# stm32hw01.net
KiCad netlist of a schematic drawn in EAGLE
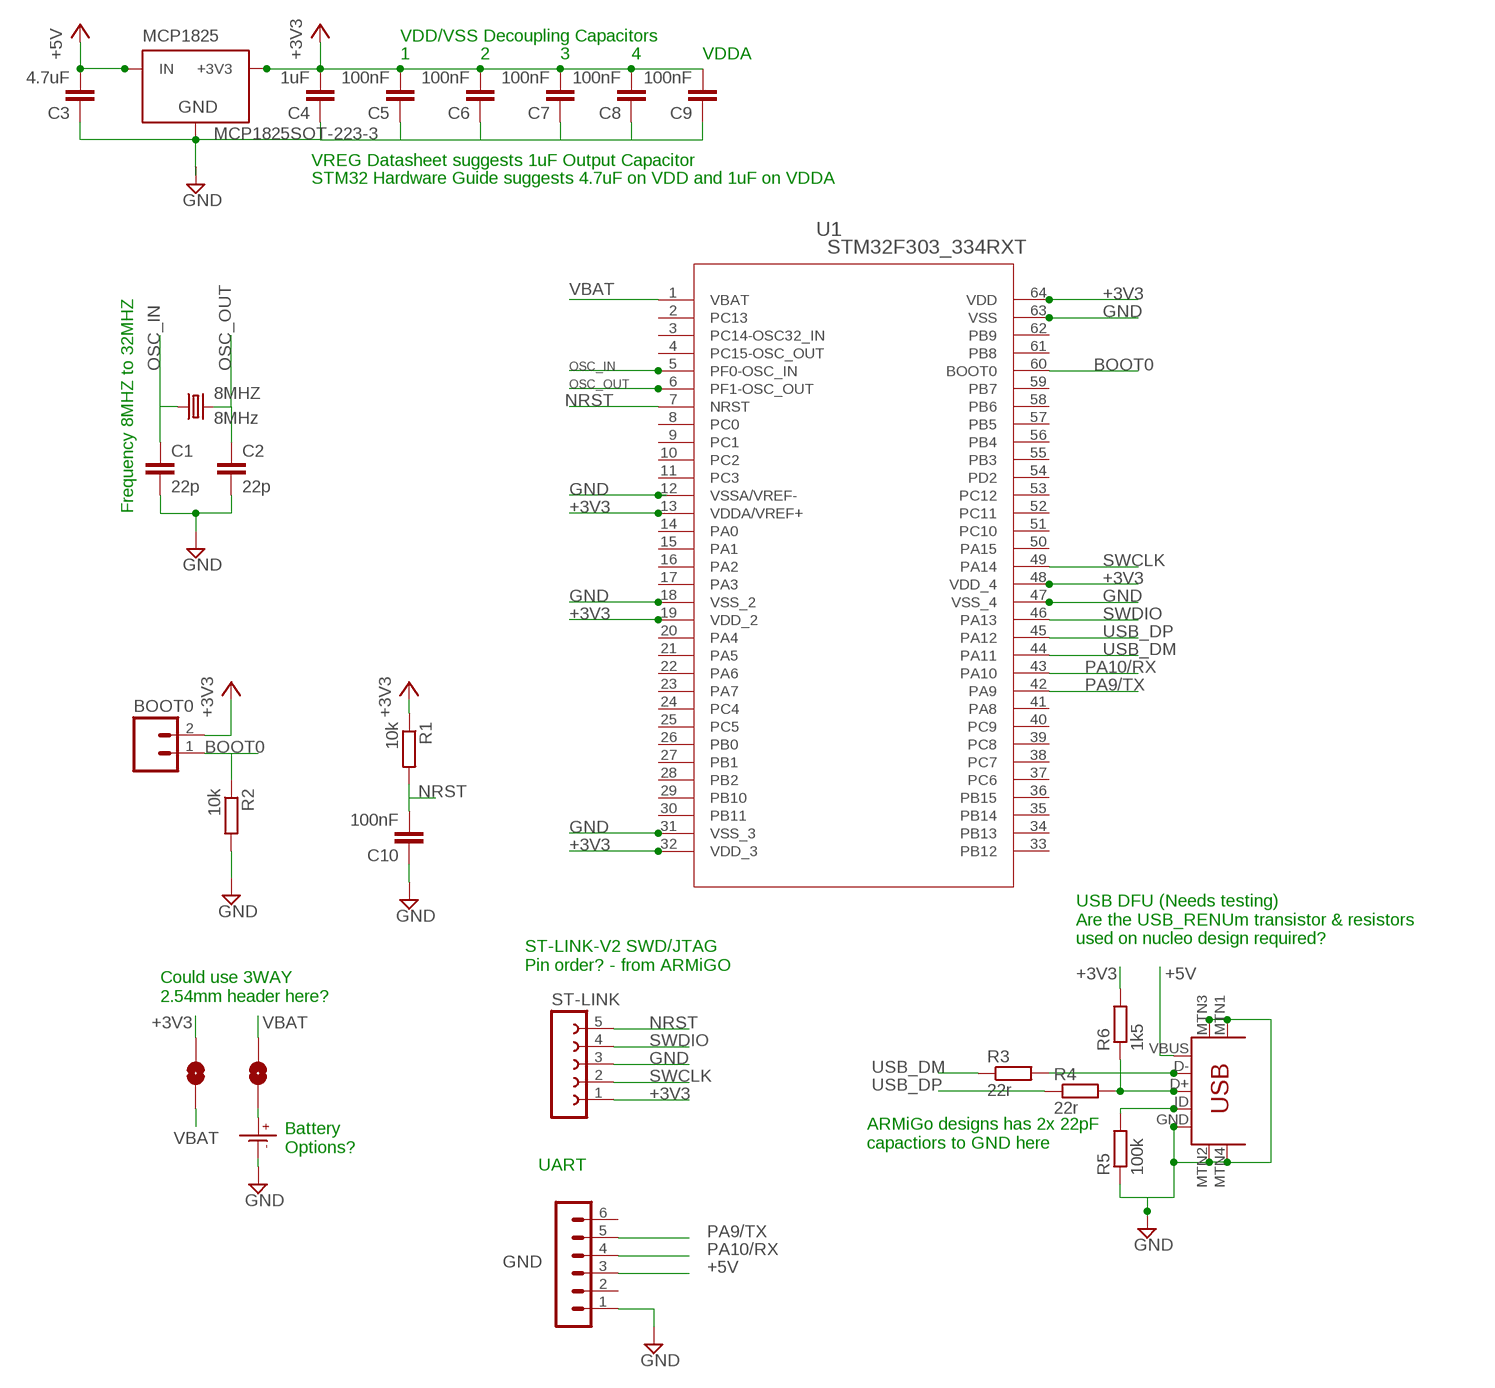
[diagram p0: schematic, sheet 1]

(export (version "E")
  (design (tool "Eeschema 10.0.6"))
  (components
    (comp (ref "3V3")
      (value "SOLDERJUMPERNO")
      (footprint "eagle-import:SJ_2S-NO")
      (libsource (lib "eagle-import") (part "SOLDERJUMPERNO"))
    )
    (comp (ref "8MHZ")
      (value "8MHz")
      (footprint "eagle-import:CRYSTAL-SMD-5X3")
      (libsource (lib "eagle-import") (part "CRYSTAL5X3"))
    )
    (comp (ref "BATTERY")
      (value "SOLDERJUMPERNO")
      (footprint "eagle-import:SJ_2S-NO")
      (libsource (lib "eagle-import") (part "SOLDERJUMPERNO"))
    )
    (comp (ref "BOOT0")
      (value "M02PTH")
      (footprint "eagle-import:1X02")
      (libsource (lib "eagle-import") (part "M02PTH"))
    )
    (comp (ref "C1")
      (value "22p")
      (footprint "eagle-import:C0603")
      (libsource (lib "eagle-import") (part "C-EUC0603"))
    )
    (comp (ref "C2")
      (value "22p")
      (footprint "eagle-import:C0603")
      (libsource (lib "eagle-import") (part "C-EUC0603"))
    )
    (comp (ref "C3")
      (value "4.7uF")
      (footprint "eagle-import:C0603")
      (libsource (lib "eagle-import") (part "C-EUC0603"))
    )
    (comp (ref "C4")
      (value "1uF")
      (footprint "eagle-import:C0603")
      (libsource (lib "eagle-import") (part "C-EUC0603"))
    )
    (comp (ref "C5")
      (value "100nF")
      (footprint "eagle-import:C0603")
      (libsource (lib "eagle-import") (part "C-EUC0603"))
    )
    (comp (ref "C6")
      (value "100nF")
      (footprint "eagle-import:C0603")
      (libsource (lib "eagle-import") (part "C-EUC0603"))
    )
    (comp (ref "C7")
      (value "100nF")
      (footprint "eagle-import:C0603")
      (libsource (lib "eagle-import") (part "C-EUC0603"))
    )
    (comp (ref "C8")
      (value "100nF")
      (footprint "eagle-import:C0603")
      (libsource (lib "eagle-import") (part "C-EUC0603"))
    )
    (comp (ref "C9")
      (value "100nF")
      (footprint "eagle-import:C0603")
      (libsource (lib "eagle-import") (part "C-EUC0603"))
    )
    (comp (ref "C10")
      (value "100nF")
      (footprint "eagle-import:C0603")
      (libsource (lib "eagle-import") (part "C-EUC0603"))
    )
    (comp (ref "CR1220")
      (value "CR1220SMD")
      (footprint "eagle-import:CR1220SMD")
      (fields (field (name "MPN") "Harwin S8411-45R"))
      (libsource (lib "eagle-import") (part "CR1220SMD"))
    )
    (comp (ref "GND")
      (value "UART")
      (footprint "eagle-import:MA06-1")
      (libsource (lib "eagle-import") (part "MA06-1"))
    )
    (comp (ref "MCP1825")
      (value "MCP1825SOT-223-3")
      (footprint "eagle-import:SOT-223")
      (libsource (lib "eagle-import") (part "MCP1825SOT-223-3"))
    )
    (comp (ref "R1")
      (value "10k")
      (footprint "eagle-import:R0603")
      (libsource (lib "eagle-import") (part "R-EU_R0603"))
    )
    (comp (ref "R2")
      (value "10k")
      (footprint "eagle-import:R0603")
      (libsource (lib "eagle-import") (part "R-EU_R0603"))
    )
    (comp (ref "R3")
      (value "22r")
      (footprint "eagle-import:R0603")
      (libsource (lib "eagle-import") (part "R-EU_R0603"))
    )
    (comp (ref "R4")
      (value "22r")
      (footprint "eagle-import:R0603")
      (libsource (lib "eagle-import") (part "R-EU_R0603"))
    )
    (comp (ref "R5")
      (value "100k")
      (footprint "eagle-import:R0603")
      (libsource (lib "eagle-import") (part "R-EU_R0603"))
    )
    (comp (ref "R6")
      (value "1k5")
      (footprint "eagle-import:R0603")
      (libsource (lib "eagle-import") (part "R-EU_R0603"))
    )
    (comp (ref "ST-LINK")
      (value "FE05-1")
      (footprint "eagle-import:FE05-1")
      (libsource (lib "eagle-import") (part "FE05-1"))
    )
    (comp (ref "U$10")
      (value "USB-MINIB-5PIN")
      (footprint "eagle-import:USB-MINIB-CISECO")
      (libsource (lib "eagle-import") (part "USB-MINIB-5PIN"))
    )
    (comp (ref "U1")
      (value "STM32F303_334RXT")
      (footprint "eagle-import:LQFP64-10X10MM")
      (fields (field (name "MANUFACTURER_PART_NUMBER") "stm32f303_334rxt"))
      (libsource (lib "eagle-import") (part "STM32F303_334RXT"))
    )
  )
  (nets
    (net (code "1") (name "+3V3") (class "Default")
      (node (ref "3V3") (pin "1") (pinfunction "1_1") (pintype "passive"))
      (node (ref "BOOT0") (pin "2") (pinfunction "2_2") (pintype "passive"))
      (node (ref "C4") (pin "2") (pinfunction "2_2") (pintype "passive"))
      (node (ref "C5") (pin "2") (pinfunction "2_2") (pintype "passive"))
      (node (ref "C6") (pin "2") (pinfunction "2_2") (pintype "passive"))
      (node (ref "C7") (pin "2") (pinfunction "2_2") (pintype "passive"))
      (node (ref "C8") (pin "2") (pinfunction "2_2") (pintype "passive"))
      (node (ref "C9") (pin "2") (pinfunction "2_2") (pintype "passive"))
      (node (ref "MCP1825") (pin "3") (pinfunction "+3V3_3") (pintype "power_in"))
      (node (ref "R1") (pin "1") (pinfunction "1_1") (pintype "passive"))
      (node (ref "R6") (pin "2") (pinfunction "2_2") (pintype "passive"))
      (node (ref "ST-LINK") (pin "1") (pinfunction "1_1") (pintype "passive"))
      (node (ref "U1") (pin "13") (pinfunction "VDDA/VREF+_13") (pintype "power_in"))
      (node (ref "U1") (pin "19") (pinfunction "VDD_2_19") (pintype "power_in"))
      (node (ref "U1") (pin "32") (pinfunction "VDD_3_32") (pintype "power_in"))
      (node (ref "U1") (pin "48") (pinfunction "VDD_4_48") (pintype "power_in"))
      (node (ref "U1") (pin "64") (pinfunction "VDD_64") (pintype "power_in"))
    )
    (net (code "2") (name "+5V") (class "Default")
      (node (ref "C3") (pin "2") (pinfunction "2_2") (pintype "passive"))
      (node (ref "GND") (pin "3") (pinfunction "3_3") (pintype "passive"))
      (node (ref "MCP1825") (pin "1") (pinfunction "IN_1") (pintype "power_in"))
      (node (ref "U$10") (pin "VBUS") (pinfunction "VBUS_VBUS") (pintype "bidirectional"))
    )
    (net (code "3") (name "/BOOT0") (class "Default")
      (node (ref "BOOT0") (pin "1") (pinfunction "1_1") (pintype "passive"))
      (node (ref "R2") (pin "1") (pinfunction "1_1") (pintype "passive"))
      (node (ref "U1") (pin "60") (pinfunction "BOOT0_60") (pintype "input"))
    )
    (net (code "4") (name "/NRST") (class "Default")
      (node (ref "C10") (pin "2") (pinfunction "2_2") (pintype "passive"))
      (node (ref "R1") (pin "2") (pinfunction "2_2") (pintype "passive"))
      (node (ref "ST-LINK") (pin "5") (pinfunction "5_5") (pintype "passive"))
      (node (ref "U1") (pin "7") (pinfunction "NRST_7") (pintype "bidirectional"))
    )
    (net (code "5") (name "/OSC_IN") (class "Default")
      (node (ref "8MHZ") (pin "1") (pinfunction "1_1") (pintype "passive"))
      (node (ref "C1") (pin "1") (pinfunction "1_1") (pintype "passive"))
      (node (ref "U1") (pin "5") (pinfunction "PF0-OSC_IN_5") (pintype "bidirectional"))
    )
    (net (code "6") (name "/OSC_OUT") (class "Default")
      (node (ref "8MHZ") (pin "3") (pinfunction "2_3") (pintype "passive"))
      (node (ref "C2") (pin "1") (pinfunction "1_1") (pintype "passive"))
      (node (ref "U1") (pin "6") (pinfunction "PF1-OSC_OUT_6") (pintype "bidirectional"))
    )
    (net (code "7") (name "/PA9{slash}TX") (class "Default")
      (node (ref "GND") (pin "5") (pinfunction "5_5") (pintype "passive"))
      (node (ref "U1") (pin "42") (pinfunction "PA9_42") (pintype "bidirectional"))
    )
    (net (code "8") (name "/PA10{slash}RX") (class "Default")
      (node (ref "GND") (pin "4") (pinfunction "4_4") (pintype "passive"))
      (node (ref "U1") (pin "43") (pinfunction "PA10_43") (pintype "bidirectional"))
    )
    (net (code "9") (name "/SWCLK") (class "Default")
      (node (ref "ST-LINK") (pin "2") (pinfunction "2_2") (pintype "passive"))
      (node (ref "U1") (pin "49") (pinfunction "PA14_49") (pintype "bidirectional"))
    )
    (net (code "10") (name "/SWDIO") (class "Default")
      (node (ref "ST-LINK") (pin "4") (pinfunction "4_4") (pintype "passive"))
      (node (ref "U1") (pin "46") (pinfunction "PA13_46") (pintype "bidirectional"))
    )
    (net (code "11") (name "/USB_DM") (class "Default")
      (node (ref "R3") (pin "1") (pinfunction "1_1") (pintype "passive"))
      (node (ref "U1") (pin "44") (pinfunction "PA11_44") (pintype "bidirectional"))
    )
    (net (code "12") (name "/USB_DP") (class "Default")
      (node (ref "R4") (pin "1") (pinfunction "1_1") (pintype "passive"))
      (node (ref "U1") (pin "45") (pinfunction "PA12_45") (pintype "bidirectional"))
    )
    (net (code "13") (name "/VBAT") (class "Default")
      (node (ref "3V3") (pin "2") (pinfunction "2_2") (pintype "passive"))
      (node (ref "BATTERY") (pin "1") (pinfunction "1_1") (pintype "passive"))
      (node (ref "U1") (pin "1") (pinfunction "VBAT_1") (pintype "power_in"))
    )
    (net (code "14") (name "GND") (class "Default")
      (node (ref "C1") (pin "2") (pinfunction "2_2") (pintype "passive"))
      (node (ref "C10") (pin "1") (pinfunction "1_1") (pintype "passive"))
      (node (ref "C2") (pin "2") (pinfunction "2_2") (pintype "passive"))
      (node (ref "C3") (pin "1") (pinfunction "1_1") (pintype "passive"))
      (node (ref "C4") (pin "1") (pinfunction "1_1") (pintype "passive"))
      (node (ref "C5") (pin "1") (pinfunction "1_1") (pintype "passive"))
      (node (ref "C6") (pin "1") (pinfunction "1_1") (pintype "passive"))
      (node (ref "C7") (pin "1") (pinfunction "1_1") (pintype "passive"))
      (node (ref "C8") (pin "1") (pinfunction "1_1") (pintype "passive"))
      (node (ref "C9") (pin "1") (pinfunction "1_1") (pintype "passive"))
      (node (ref "CR1220") (pin "P-") (pinfunction "P$-_P-") (pintype "bidirectional"))
      (node (ref "GND") (pin "1") (pinfunction "1_1") (pintype "passive"))
      (node (ref "MCP1825") (pin "2") (pinfunction "GND_2") (pintype "power_in"))
      (node (ref "R2") (pin "2") (pinfunction "2_2") (pintype "passive"))
      (node (ref "R5") (pin "1") (pinfunction "1_1") (pintype "passive"))
      (node (ref "ST-LINK") (pin "3") (pinfunction "3_3") (pintype "passive"))
      (node (ref "U$10") (pin "GND") (pinfunction "GND_GND") (pintype "bidirectional"))
      (node (ref "U$10") (pin "MTN1") (pinfunction "MTN2_MTN1") (pintype "bidirectional"))
      (node (ref "U$10") (pin "MTN2") (pinfunction "MTN3_MTN2") (pintype "bidirectional"))
      (node (ref "U$10") (pin "MTN3") (pinfunction "MTN1_MTN3") (pintype "bidirectional"))
      (node (ref "U$10") (pin "MTN4") (pinfunction "MTN4_MTN4") (pintype "bidirectional"))
      (node (ref "U1") (pin "12") (pinfunction "VSSA/VREF-_12") (pintype "power_in"))
      (node (ref "U1") (pin "18") (pinfunction "VSS_2_18") (pintype "power_in"))
      (node (ref "U1") (pin "31") (pinfunction "VSS_3_31") (pintype "power_in"))
      (node (ref "U1") (pin "47") (pinfunction "VSS_4_47") (pintype "power_in"))
      (node (ref "U1") (pin "63") (pinfunction "VSS_63") (pintype "power_in"))
    )
    (net (code "15") (name "Net-(CR1220-P$+)") (class "Default")
      (node (ref "BATTERY") (pin "2") (pinfunction "2_2") (pintype "passive"))
      (node (ref "CR1220") (pin "P+") (pinfunction "P$+_P+") (pintype "bidirectional"))
    )
    (net (code "16") (name "Net-(R3-Pad2)") (class "Default")
      (node (ref "R3") (pin "2") (pinfunction "2_2") (pintype "passive"))
      (node (ref "U$10") (pin "D-") (pinfunction "D-_D-") (pintype "bidirectional"))
    )
    (net (code "17") (name "Net-(R4-Pad2)") (class "Default")
      (node (ref "R4") (pin "2") (pinfunction "2_2") (pintype "passive"))
      (node (ref "R6") (pin "1") (pinfunction "1_1") (pintype "passive"))
      (node (ref "U$10") (pin "D+") (pinfunction "D+_D+") (pintype "bidirectional"))
    )
    (net (code "18") (name "Net-(R5-Pad2)") (class "Default")
      (node (ref "R5") (pin "2") (pinfunction "2_2") (pintype "passive"))
      (node (ref "U$10") (pin "ID") (pinfunction "ID_ID") (pintype "bidirectional"))
    )
    (net (code "19") (name "unconnected-(GND-Pad2)") (class "Default")
      (node (ref "GND") (pin "2") (pinfunction "2_2") (pintype "passive"))
    )
    (net (code "20") (name "unconnected-(GND-Pad6)") (class "Default")
      (node (ref "GND") (pin "6") (pinfunction "6_6") (pintype "passive"))
    )
    (net (code "21") (name "unconnected-(U1-PA0-Pad14)") (class "Default")
      (node (ref "U1") (pin "14") (pinfunction "PA0_14") (pintype "bidirectional"))
    )
    (net (code "22") (name "unconnected-(U1-PA1-Pad15)") (class "Default")
      (node (ref "U1") (pin "15") (pinfunction "PA1_15") (pintype "bidirectional"))
    )
    (net (code "23") (name "unconnected-(U1-PA2-Pad16)") (class "Default")
      (node (ref "U1") (pin "16") (pinfunction "PA2_16") (pintype "bidirectional"))
    )
    (net (code "24") (name "unconnected-(U1-PA3-Pad17)") (class "Default")
      (node (ref "U1") (pin "17") (pinfunction "PA3_17") (pintype "bidirectional"))
    )
    (net (code "25") (name "unconnected-(U1-PA4-Pad20)") (class "Default")
      (node (ref "U1") (pin "20") (pinfunction "PA4_20") (pintype "bidirectional"))
    )
    (net (code "26") (name "unconnected-(U1-PA5-Pad21)") (class "Default")
      (node (ref "U1") (pin "21") (pinfunction "PA5_21") (pintype "bidirectional"))
    )
    (net (code "27") (name "unconnected-(U1-PA6-Pad22)") (class "Default")
      (node (ref "U1") (pin "22") (pinfunction "PA6_22") (pintype "bidirectional"))
    )
    (net (code "28") (name "unconnected-(U1-PA7-Pad23)") (class "Default")
      (node (ref "U1") (pin "23") (pinfunction "PA7_23") (pintype "bidirectional"))
    )
    (net (code "29") (name "unconnected-(U1-PA8-Pad41)") (class "Default")
      (node (ref "U1") (pin "41") (pinfunction "PA8_41") (pintype "bidirectional"))
    )
    (net (code "30") (name "unconnected-(U1-PA15-Pad50)") (class "Default")
      (node (ref "U1") (pin "50") (pinfunction "PA15_50") (pintype "bidirectional"))
    )
    (net (code "31") (name "unconnected-(U1-PB0-Pad26)") (class "Default")
      (node (ref "U1") (pin "26") (pinfunction "PB0_26") (pintype "bidirectional"))
    )
    (net (code "32") (name "unconnected-(U1-PB1-Pad27)") (class "Default")
      (node (ref "U1") (pin "27") (pinfunction "PB1_27") (pintype "bidirectional"))
    )
    (net (code "33") (name "unconnected-(U1-PB2-Pad28)") (class "Default")
      (node (ref "U1") (pin "28") (pinfunction "PB2_28") (pintype "bidirectional"))
    )
    (net (code "34") (name "unconnected-(U1-PB3-Pad55)") (class "Default")
      (node (ref "U1") (pin "55") (pinfunction "PB3_55") (pintype "bidirectional"))
    )
    (net (code "35") (name "unconnected-(U1-PB4-Pad56)") (class "Default")
      (node (ref "U1") (pin "56") (pinfunction "PB4_56") (pintype "bidirectional"))
    )
    (net (code "36") (name "unconnected-(U1-PB5-Pad57)") (class "Default")
      (node (ref "U1") (pin "57") (pinfunction "PB5_57") (pintype "bidirectional"))
    )
    (net (code "37") (name "unconnected-(U1-PB6-Pad58)") (class "Default")
      (node (ref "U1") (pin "58") (pinfunction "PB6_58") (pintype "bidirectional"))
    )
    (net (code "38") (name "unconnected-(U1-PB7-Pad59)") (class "Default")
      (node (ref "U1") (pin "59") (pinfunction "PB7_59") (pintype "bidirectional"))
    )
    (net (code "39") (name "unconnected-(U1-PB8-Pad61)") (class "Default")
      (node (ref "U1") (pin "61") (pinfunction "PB8_61") (pintype "bidirectional"))
    )
    (net (code "40") (name "unconnected-(U1-PB9-Pad62)") (class "Default")
      (node (ref "U1") (pin "62") (pinfunction "PB9_62") (pintype "bidirectional"))
    )
    (net (code "41") (name "unconnected-(U1-PB10-Pad29)") (class "Default")
      (node (ref "U1") (pin "29") (pinfunction "PB10_29") (pintype "bidirectional"))
    )
    (net (code "42") (name "unconnected-(U1-PB11-Pad30)") (class "Default")
      (node (ref "U1") (pin "30") (pinfunction "PB11_30") (pintype "bidirectional"))
    )
    (net (code "43") (name "unconnected-(U1-PB12-Pad33)") (class "Default")
      (node (ref "U1") (pin "33") (pinfunction "PB12_33") (pintype "bidirectional"))
    )
    (net (code "44") (name "unconnected-(U1-PB13-Pad34)") (class "Default")
      (node (ref "U1") (pin "34") (pinfunction "PB13_34") (pintype "bidirectional"))
    )
    (net (code "45") (name "unconnected-(U1-PB14-Pad35)") (class "Default")
      (node (ref "U1") (pin "35") (pinfunction "PB14_35") (pintype "bidirectional"))
    )
    (net (code "46") (name "unconnected-(U1-PB15-Pad36)") (class "Default")
      (node (ref "U1") (pin "36") (pinfunction "PB15_36") (pintype "bidirectional"))
    )
    (net (code "47") (name "unconnected-(U1-PC0-Pad8)") (class "Default")
      (node (ref "U1") (pin "8") (pinfunction "PC0_8") (pintype "bidirectional"))
    )
    (net (code "48") (name "unconnected-(U1-PC1-Pad9)") (class "Default")
      (node (ref "U1") (pin "9") (pinfunction "PC1_9") (pintype "bidirectional"))
    )
    (net (code "49") (name "unconnected-(U1-PC2-Pad10)") (class "Default")
      (node (ref "U1") (pin "10") (pinfunction "PC2_10") (pintype "bidirectional"))
    )
    (net (code "50") (name "unconnected-(U1-PC3-Pad11)") (class "Default")
      (node (ref "U1") (pin "11") (pinfunction "PC3_11") (pintype "bidirectional"))
    )
    (net (code "51") (name "unconnected-(U1-PC4-Pad24)") (class "Default")
      (node (ref "U1") (pin "24") (pinfunction "PC4_24") (pintype "bidirectional"))
    )
    (net (code "52") (name "unconnected-(U1-PC5-Pad25)") (class "Default")
      (node (ref "U1") (pin "25") (pinfunction "PC5_25") (pintype "bidirectional"))
    )
    (net (code "53") (name "unconnected-(U1-PC6-Pad37)") (class "Default")
      (node (ref "U1") (pin "37") (pinfunction "PC6_37") (pintype "bidirectional"))
    )
    (net (code "54") (name "unconnected-(U1-PC7-Pad38)") (class "Default")
      (node (ref "U1") (pin "38") (pinfunction "PC7_38") (pintype "bidirectional"))
    )
    (net (code "55") (name "unconnected-(U1-PC8-Pad39)") (class "Default")
      (node (ref "U1") (pin "39") (pinfunction "PC8_39") (pintype "bidirectional"))
    )
    (net (code "56") (name "unconnected-(U1-PC9-Pad40)") (class "Default")
      (node (ref "U1") (pin "40") (pinfunction "PC9_40") (pintype "bidirectional"))
    )
    (net (code "57") (name "unconnected-(U1-PC10-Pad51)") (class "Default")
      (node (ref "U1") (pin "51") (pinfunction "PC10_51") (pintype "bidirectional"))
    )
    (net (code "58") (name "unconnected-(U1-PC11-Pad52)") (class "Default")
      (node (ref "U1") (pin "52") (pinfunction "PC11_52") (pintype "bidirectional"))
    )
    (net (code "59") (name "unconnected-(U1-PC12-Pad53)") (class "Default")
      (node (ref "U1") (pin "53") (pinfunction "PC12_53") (pintype "bidirectional"))
    )
    (net (code "60") (name "unconnected-(U1-PC13-Pad2)") (class "Default")
      (node (ref "U1") (pin "2") (pinfunction "PC13_2") (pintype "bidirectional"))
    )
    (net (code "61") (name "unconnected-(U1-PC14-OSC32_IN-Pad3)") (class "Default")
      (node (ref "U1") (pin "3") (pinfunction "PC14-OSC32_IN_3") (pintype "bidirectional"))
    )
    (net (code "62") (name "unconnected-(U1-PC15-OSC_OUT-Pad4)") (class "Default")
      (node (ref "U1") (pin "4") (pinfunction "PC15-OSC_OUT_4") (pintype "bidirectional"))
    )
    (net (code "63") (name "unconnected-(U1-PD2-Pad54)") (class "Default")
      (node (ref "U1") (pin "54") (pinfunction "PD2_54") (pintype "bidirectional"))
    )
  )
)
